# Main.net
KiCad netlist of a schematic drawn in Altium Designer
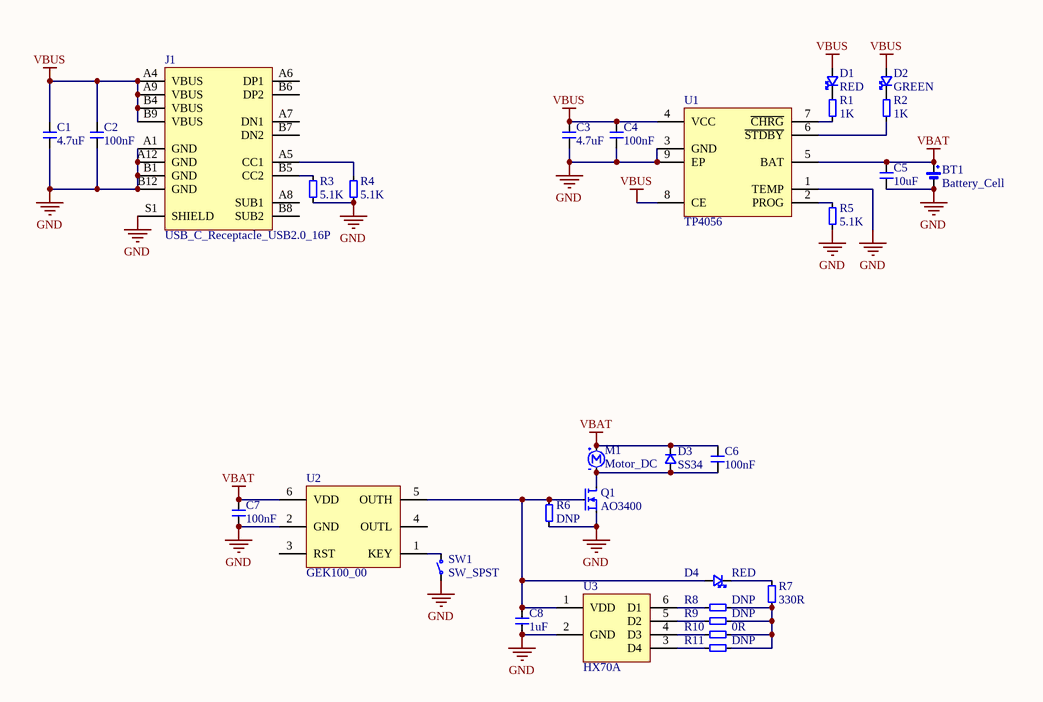
[diagram p0: Main.SchDoc]

(export (version "E")
  (design (tool "Eeschema 10.0.6"))
  (components
    (comp (ref "BT1")
      (value "Battery_Cell")
      (footprint "WAFER-PH2.0-2PWB")
      (description "Single-cell battery")
      (libsource (lib "temporary") (part "Battery_Cell"))
    )
    (comp (ref "C1")
      (value "4.7uF")
      (footprint "C_0603_1608Metric")
      (description "Unpolarized capacitor")
      (libsource (lib "temporary") (part "C"))
    )
    (comp (ref "C2")
      (value "100nF")
      (footprint "C_0402_1005Metric")
      (description "Unpolarized capacitor")
      (libsource (lib "temporary") (part "C"))
    )
    (comp (ref "C3")
      (value "4.7uF")
      (footprint "C_0603_1608Metric")
      (description "Unpolarized capacitor")
      (libsource (lib "temporary") (part "C"))
    )
    (comp (ref "C4")
      (value "100nF")
      (footprint "C_0402_1005Metric")
      (description "Unpolarized capacitor")
      (libsource (lib "temporary") (part "C"))
    )
    (comp (ref "C5")
      (value "10uF")
      (footprint "C_0603_1608Metric")
      (description "Unpolarized capacitor")
      (libsource (lib "temporary") (part "C"))
    )
    (comp (ref "C6")
      (value "100nF")
      (footprint "C_0402_1005Metric")
      (description "Unpolarized capacitor")
      (libsource (lib "temporary") (part "C"))
    )
    (comp (ref "C7")
      (value "100nF")
      (footprint "C_0402_1005Metric")
      (description "Unpolarized capacitor")
      (libsource (lib "temporary") (part "C"))
    )
    (comp (ref "C8")
      (value "1uF")
      (footprint "C_0603_1608Metric")
      (description "Unpolarized capacitor")
      (libsource (lib "temporary") (part "C"))
    )
    (comp (ref "D1")
      (value "RED")
      (footprint "LED_0603_1608Metric")
      (description "Light emitting diode")
      (libsource (lib "temporary") (part "LED"))
    )
    (comp (ref "D2")
      (value "GREEN")
      (footprint "LED_0603_1608Metric")
      (description "Light emitting diode")
      (libsource (lib "temporary") (part "LED"))
    )
    (comp (ref "D3")
      (value "SS34")
      (footprint "D_SMA")
      (description "diode")
      (libsource (lib "temporary") (part "D"))
    )
    (comp (ref "D4")
      (value "RED")
      (footprint "LED_0603_1608Metric")
      (description "Light emitting diode")
      (libsource (lib "temporary") (part "LED"))
    )
    (comp (ref "J1")
      (value "USB_C_Receptacle_USB2.0_16P")
      (footprint "USB_C_Receptacle_GCT_USB4105-xx-A_16P_TopMnt_Horizontal")
      (description "USB 2.0-only 16P Type-C Receptacle connector")
      (libsource (lib "temporary") (part "USB_C_Receptacle_USB2.0_16P"))
    )
    (comp (ref "M1")
      (value "Motor_DC")
      (footprint "Motor-HJD-3.7V-500mA")
      (description "DC Motor")
      (libsource (lib "temporary") (part "Motor_DC"))
    )
    (comp (ref "Q1")
      (value "AO3400")
      (footprint "SOT-23-3")
      (description "N-MOSFET transistor, gate/source/drain")
      (libsource (lib "temporary") (part "Q_NMOS_GSD"))
    )
    (comp (ref "R1")
      (value "1K")
      (footprint "R_0402_1005Metric")
      (description "Resistor")
      (libsource (lib "temporary") (part "R"))
    )
    (comp (ref "R2")
      (value "1K")
      (footprint "R_0402_1005Metric")
      (description "Resistor")
      (libsource (lib "temporary") (part "R"))
    )
    (comp (ref "R3")
      (value "5.1K")
      (footprint "R_0402_1005Metric")
      (description "Resistor")
      (libsource (lib "temporary") (part "R"))
    )
    (comp (ref "R4")
      (value "5.1K")
      (footprint "R_0402_1005Metric")
      (description "Resistor")
      (libsource (lib "temporary") (part "R"))
    )
    (comp (ref "R5")
      (value "5.1K")
      (footprint "R_0402_1005Metric")
      (description "Resistor")
      (libsource (lib "temporary") (part "R"))
    )
    (comp (ref "R6")
      (value "DNP")
      (footprint "R_0402_1005Metric")
      (description "Resistor")
      (libsource (lib "temporary") (part "R"))
    )
    (comp (ref "R7")
      (value "330R")
      (footprint "R_0402_1005Metric")
      (description "Resistor")
      (libsource (lib "temporary") (part "R"))
    )
    (comp (ref "R8")
      (value "DNP")
      (footprint "R_0402_1005Metric")
      (description "Resistor")
      (libsource (lib "temporary") (part "R"))
    )
    (comp (ref "R9")
      (value "DNP")
      (footprint "R_0402_1005Metric")
      (description "Resistor")
      (libsource (lib "temporary") (part "R"))
    )
    (comp (ref "R10")
      (value "0R")
      (footprint "R_0402_1005Metric")
      (description "Resistor")
      (libsource (lib "temporary") (part "R"))
    )
    (comp (ref "R11")
      (value "DNP")
      (footprint "R_0402_1005Metric")
      (description "Resistor")
      (libsource (lib "temporary") (part "R"))
    )
    (comp (ref "SW1")
      (value "SW_SPST")
      (footprint "SW_PUSH_6mm_H5mm")
      (description "Single Pole Single Throw (SPST) switch")
      (libsource (lib "temporary") (part "SW_SPST"))
    )
    (comp (ref "U1")
      (value "TP4056")
      (footprint "EMSOP-8-1EP_3x3mm_P0.65mm_EP1.7x1.9mm")
      (libsource (lib "temporary") (part "TP4056"))
    )
    (comp (ref "U2")
      (value "GEK100_00")
      (footprint "SOT-23-6")
      (description "Push-button power controller, hardware on/off, SOT-23-6")
      (libsource (lib "temporary") (part "GEK100_xx"))
    )
    (comp (ref "U3") (value "HX70A") (footprint "SOT-23-6") (libsource (lib "temporary") (part "HX70A")))
  )
  (nets
    (net (code "1") (name "GND") (class "Default")
      (node (ref "BT1") (pin "1") (pinfunction "1_1") (pintype "passive"))
      (node (ref "C1") (pin "2") (pinfunction "2_2") (pintype "passive"))
      (node (ref "C2") (pin "2") (pinfunction "2_2") (pintype "passive"))
      (node (ref "C3") (pin "2") (pinfunction "2_2") (pintype "passive"))
      (node (ref "C4") (pin "2") (pinfunction "2_2") (pintype "passive"))
      (node (ref "C5") (pin "2") (pinfunction "2_2") (pintype "passive"))
      (node (ref "C7") (pin "2") (pinfunction "2_2") (pintype "passive"))
      (node (ref "C8") (pin "2") (pinfunction "2_2") (pintype "passive"))
      (node (ref "J1") (pin "A1") (pinfunction "GND_A1") (pintype "passive"))
      (node (ref "J1") (pin "A12") (pinfunction "GND_A12") (pintype "passive"))
      (node (ref "J1") (pin "B1") (pinfunction "GND_B1") (pintype "passive"))
      (node (ref "J1") (pin "B12") (pinfunction "GND_B12") (pintype "passive"))
      (node (ref "J1") (pin "S1") (pinfunction "SHIELD_S1") (pintype "passive"))
      (node (ref "Q1") (pin "2") (pinfunction "S_2") (pintype "passive"))
      (node (ref "R3") (pin "2") (pinfunction "2_2") (pintype "passive"))
      (node (ref "R4") (pin "2") (pinfunction "2_2") (pintype "passive"))
      (node (ref "R5") (pin "2") (pinfunction "2_2") (pintype "passive"))
      (node (ref "R6") (pin "2") (pinfunction "2_2") (pintype "passive"))
      (node (ref "SW1") (pin "1") (pinfunction "1_1") (pintype "passive"))
      (node (ref "U1") (pin "1") (pinfunction "TEMP_1") (pintype "passive"))
      (node (ref "U1") (pin "3") (pinfunction "GND_3") (pintype "passive"))
      (node (ref "U1") (pin "9") (pinfunction "EP_9") (pintype "passive"))
      (node (ref "U2") (pin "2") (pinfunction "GND_2") (pintype "passive"))
      (node (ref "U3") (pin "2") (pinfunction "GND_2") (pintype "passive"))
    )
    (net (code "2") (name "Net-(D1-K)") (class "Default")
      (node (ref "D1") (pin "1") (pinfunction "K_1") (pintype "passive"))
      (node (ref "R1") (pin "1") (pinfunction "1_1") (pintype "passive"))
    )
    (net (code "3") (name "Net-(D2-K)") (class "Default")
      (node (ref "D2") (pin "1") (pinfunction "K_1") (pintype "passive"))
      (node (ref "R2") (pin "1") (pinfunction "1_1") (pintype "passive"))
    )
    (net (code "4") (name "Net-(D4-A)") (class "Default")
      (node (ref "C8") (pin "1") (pinfunction "1_1") (pintype "passive"))
      (node (ref "D4") (pin "2") (pinfunction "A_2") (pintype "passive"))
      (node (ref "Q1") (pin "1") (pinfunction "G_1") (pintype "passive"))
      (node (ref "R6") (pin "1") (pinfunction "1_1") (pintype "passive"))
      (node (ref "U2") (pin "5") (pinfunction "OUTH_5") (pintype "passive"))
      (node (ref "U3") (pin "1") (pinfunction "VDD_1") (pintype "passive"))
    )
    (net (code "5") (name "Net-(D4-K)") (class "Default")
      (node (ref "D4") (pin "1") (pinfunction "K_1") (pintype "passive"))
      (node (ref "R7") (pin "2") (pinfunction "2_2") (pintype "passive"))
    )
    (net (code "6") (name "Net-(J1-CC1)") (class "Default")
      (node (ref "J1") (pin "A5") (pinfunction "CC1_A5") (pintype "passive"))
      (node (ref "R4") (pin "1") (pinfunction "1_1") (pintype "passive"))
    )
    (net (code "7") (name "Net-(J1-CC2)") (class "Default")
      (node (ref "J1") (pin "B5") (pinfunction "CC2_B5") (pintype "passive"))
      (node (ref "R3") (pin "1") (pinfunction "1_1") (pintype "passive"))
    )
    (net (code "8") (name "Net-(Q1-D)") (class "Default")
      (node (ref "C6") (pin "2") (pinfunction "2_2") (pintype "passive"))
      (node (ref "D3") (pin "2") (pinfunction "2_2") (pintype "passive"))
      (node (ref "M1") (pin "2") (pinfunction "2_2") (pintype "passive"))
      (node (ref "Q1") (pin "3") (pinfunction "D_3") (pintype "passive"))
    )
    (net (code "9") (name "Net-(R10-Pad2)") (class "Default")
      (node (ref "R10") (pin "2") (pinfunction "2_2") (pintype "passive"))
      (node (ref "R11") (pin "2") (pinfunction "2_2") (pintype "passive"))
      (node (ref "R7") (pin "1") (pinfunction "1_1") (pintype "passive"))
      (node (ref "R8") (pin "2") (pinfunction "2_2") (pintype "passive"))
      (node (ref "R9") (pin "2") (pinfunction "2_2") (pintype "passive"))
    )
    (net (code "10") (name "Net-(U1-PROG)") (class "Default")
      (node (ref "R5") (pin "1") (pinfunction "1_1") (pintype "passive"))
      (node (ref "U1") (pin "2") (pinfunction "PROG_2") (pintype "passive"))
    )
    (net (code "11") (name "Net-(U1-~{CHRG})") (class "Default")
      (node (ref "R1") (pin "2") (pinfunction "2_2") (pintype "passive"))
      (node (ref "U1") (pin "7") (pinfunction "~{CHRG}_7") (pintype "passive"))
    )
    (net (code "12") (name "Net-(U1-~{STDBY})") (class "Default")
      (node (ref "R2") (pin "2") (pinfunction "2_2") (pintype "passive"))
      (node (ref "U1") (pin "6") (pinfunction "~{STDBY}_6") (pintype "passive"))
    )
    (net (code "13") (name "Net-(U2-KEY)") (class "Default")
      (node (ref "SW1") (pin "2") (pinfunction "2_2") (pintype "passive"))
      (node (ref "U2") (pin "1") (pinfunction "KEY_1") (pintype "passive"))
    )
    (net (code "14") (name "Net-(U3-D1)") (class "Default")
      (node (ref "R8") (pin "1") (pinfunction "1_1") (pintype "passive"))
      (node (ref "U3") (pin "6") (pinfunction "D1_6") (pintype "passive"))
    )
    (net (code "15") (name "Net-(U3-D2)") (class "Default")
      (node (ref "R9") (pin "1") (pinfunction "1_1") (pintype "passive"))
      (node (ref "U3") (pin "5") (pinfunction "D2_5") (pintype "passive"))
    )
    (net (code "16") (name "Net-(U3-D3)") (class "Default")
      (node (ref "R10") (pin "1") (pinfunction "1_1") (pintype "passive"))
      (node (ref "U3") (pin "4") (pinfunction "D3_4") (pintype "passive"))
    )
    (net (code "17") (name "Net-(U3-D4)") (class "Default")
      (node (ref "R11") (pin "1") (pinfunction "1_1") (pintype "passive"))
      (node (ref "U3") (pin "3") (pinfunction "D4_3") (pintype "passive"))
    )
    (net (code "18") (name "VBAT") (class "Default")
      (node (ref "BT1") (pin "2") (pinfunction "2_2") (pintype "passive"))
      (node (ref "C5") (pin "1") (pinfunction "1_1") (pintype "passive"))
      (node (ref "C6") (pin "1") (pinfunction "1_1") (pintype "passive"))
      (node (ref "C7") (pin "1") (pinfunction "1_1") (pintype "passive"))
      (node (ref "D3") (pin "1") (pinfunction "1_1") (pintype "passive"))
      (node (ref "M1") (pin "1") (pinfunction "1_1") (pintype "passive"))
      (node (ref "U1") (pin "5") (pinfunction "BAT_5") (pintype "passive"))
      (node (ref "U2") (pin "6") (pinfunction "VDD_6") (pintype "passive"))
    )
    (net (code "19") (name "VBUS") (class "Default")
      (node (ref "C1") (pin "1") (pinfunction "1_1") (pintype "passive"))
      (node (ref "C2") (pin "1") (pinfunction "1_1") (pintype "passive"))
      (node (ref "C3") (pin "1") (pinfunction "1_1") (pintype "passive"))
      (node (ref "C4") (pin "1") (pinfunction "1_1") (pintype "passive"))
      (node (ref "D1") (pin "2") (pinfunction "A_2") (pintype "passive"))
      (node (ref "D2") (pin "2") (pinfunction "A_2") (pintype "passive"))
      (node (ref "J1") (pin "A4") (pinfunction "VBUS_A4") (pintype "passive"))
      (node (ref "J1") (pin "A9") (pinfunction "VBUS_A9") (pintype "passive"))
      (node (ref "J1") (pin "B4") (pinfunction "VBUS_B4") (pintype "passive"))
      (node (ref "J1") (pin "B9") (pinfunction "VBUS_B9") (pintype "passive"))
      (node (ref "U1") (pin "4") (pinfunction "VCC_4") (pintype "passive"))
      (node (ref "U1") (pin "8") (pinfunction "CE_8") (pintype "passive"))
    )
    (net (code "20") (name "unconnected-(J1-DN1-PadA7)") (class "Default")
      (node (ref "J1") (pin "A7") (pinfunction "DN1_A7") (pintype "passive"))
    )
    (net (code "21") (name "unconnected-(J1-DN2-PadB7)") (class "Default")
      (node (ref "J1") (pin "B7") (pinfunction "DN2_B7") (pintype "passive"))
    )
    (net (code "22") (name "unconnected-(J1-DP1-PadA6)") (class "Default")
      (node (ref "J1") (pin "A6") (pinfunction "DP1_A6") (pintype "passive"))
    )
    (net (code "23") (name "unconnected-(J1-DP2-PadB6)") (class "Default")
      (node (ref "J1") (pin "B6") (pinfunction "DP2_B6") (pintype "passive"))
    )
    (net (code "24") (name "unconnected-(J1-SUB1-PadA8)") (class "Default")
      (node (ref "J1") (pin "A8") (pinfunction "SUB1_A8") (pintype "passive"))
    )
    (net (code "25") (name "unconnected-(J1-SUB2-PadB8)") (class "Default")
      (node (ref "J1") (pin "B8") (pinfunction "SUB2_B8") (pintype "passive"))
    )
    (net (code "26") (name "unconnected-(U2-OUTL-Pad4)") (class "Default")
      (node (ref "U2") (pin "4") (pinfunction "OUTL_4") (pintype "passive"))
    )
    (net (code "27") (name "unconnected-(U2-RST-Pad3)") (class "Default")
      (node (ref "U2") (pin "3") (pinfunction "RST_3") (pintype "passive"))
    )
  )
)
